# MXCHipConnector.net
KiCad netlist of a schematic drawn in EAGLE
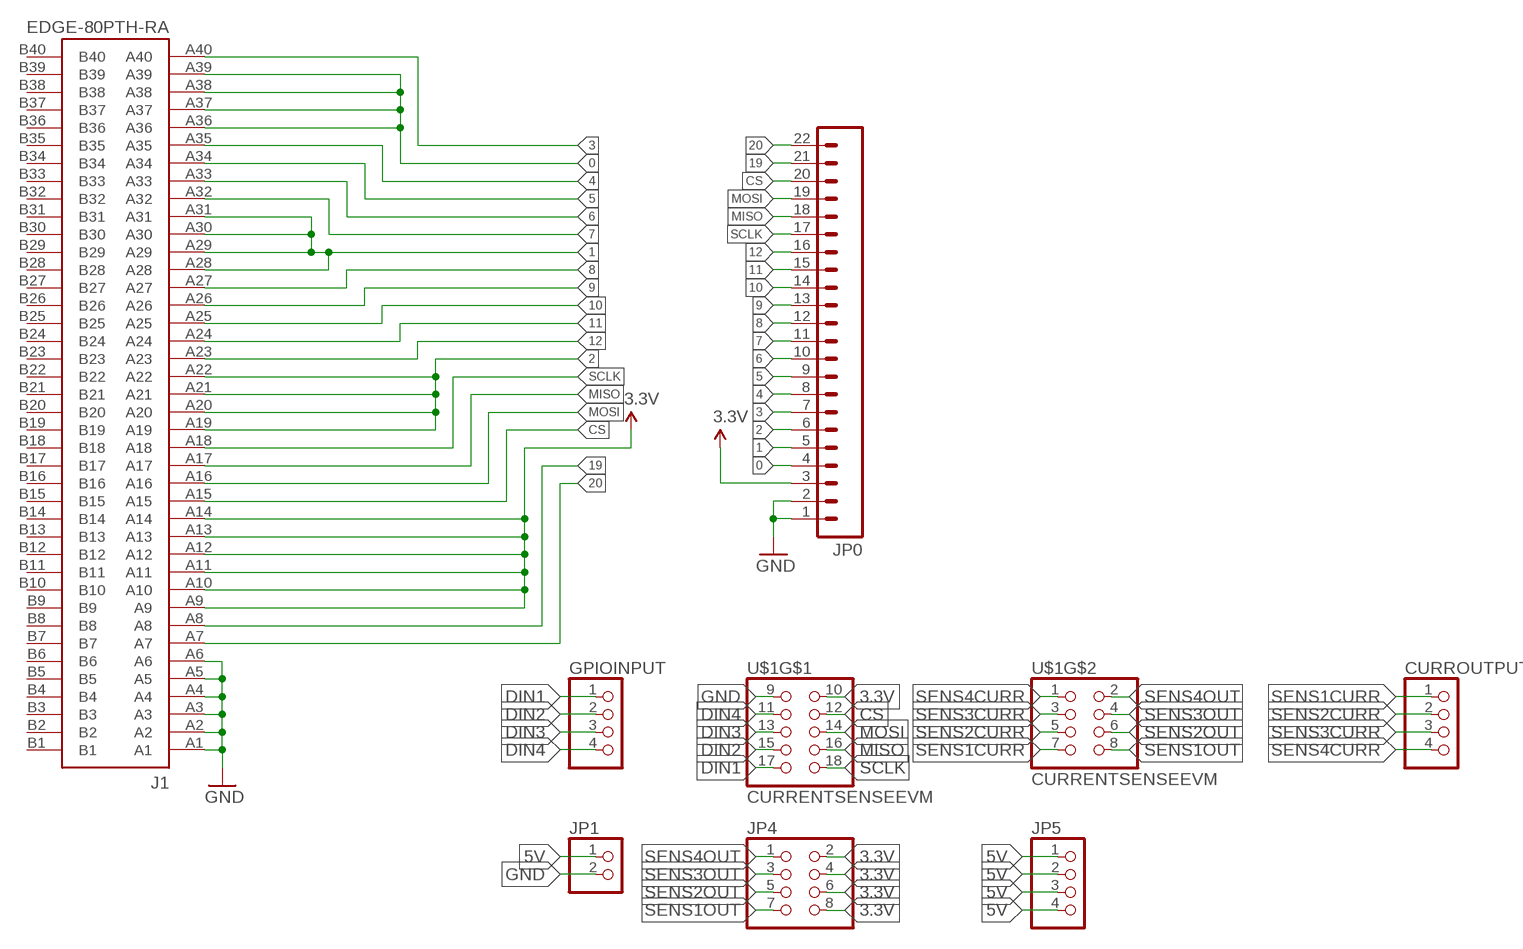
[diagram p0: schematic, sheet 1]

(export (version "E")
  (design (tool "Eeschema 10.0.6"))
  (components
    (comp (ref "CURROUTPUT")
      (value "PINHD-1X4")
      (footprint "eagle-import:1X04")
      (libsource (lib "eagle-import") (part "PINHD-1X4"))
    )
    (comp (ref "GPIOINPUT")
      (value "PINHD-1X4")
      (footprint "eagle-import:1X04")
      (libsource (lib "eagle-import") (part "PINHD-1X4"))
    )
    (comp (ref "J1")
      (value "EDGE-80PTH-RA")
      (footprint "eagle-import:VEC-127-080-R")
      (libsource (lib "eagle-import") (part "EDGE-80PTH-RA"))
    )
    (comp (ref "JP0")
      (value "M22PTH")
      (footprint "eagle-import:1X22")
      (libsource (lib "eagle-import") (part "M22PTH"))
    )
    (comp (ref "JP1")
      (value "PINHD-1X2")
      (footprint "eagle-import:1X02")
      (libsource (lib "eagle-import") (part "PINHD-1X2"))
    )
    (comp (ref "JP4")
      (value "PINHD-2X4")
      (footprint "eagle-import:2X04")
      (libsource (lib "eagle-import") (part "PINHD-2X4"))
    )
    (comp (ref "JP5")
      (value "PINHD-1X4")
      (footprint "eagle-import:1X04")
      (libsource (lib "eagle-import") (part "PINHD-1X4"))
    )
    (comp (ref "U$1")
      (value "CURRENTSENSEEVM")
      (footprint "eagle-import:CURRENTSENSEEVM")
      (libsource (lib "eagle-import") (part "CURRENTSENSEEVM"))
    )
  )
  (nets
    (net (code "1") (name "0") (class "Default")
      (node (ref "J1") (pin "A36") (pinfunction "A36_A36") (pintype "bidirectional"))
      (node (ref "J1") (pin "A37") (pinfunction "A37_A37") (pintype "bidirectional"))
      (node (ref "J1") (pin "A38") (pinfunction "A38_A38") (pintype "bidirectional"))
      (node (ref "J1") (pin "A39") (pinfunction "A39_A39") (pintype "bidirectional"))
      (node (ref "JP0") (pin "4") (pinfunction "4_4") (pintype "passive"))
    )
    (net (code "2") (name "1") (class "Default")
      (node (ref "J1") (pin "A28") (pinfunction "A28_A28") (pintype "bidirectional"))
      (node (ref "J1") (pin "A29") (pinfunction "A29_A29") (pintype "bidirectional"))
      (node (ref "J1") (pin "A30") (pinfunction "A30_A30") (pintype "bidirectional"))
      (node (ref "J1") (pin "A31") (pinfunction "A31_A31") (pintype "bidirectional"))
      (node (ref "JP0") (pin "5") (pinfunction "5_5") (pintype "passive"))
    )
    (net (code "3") (name "2") (class "Default")
      (node (ref "J1") (pin "A19") (pinfunction "A19_A19") (pintype "bidirectional"))
      (node (ref "J1") (pin "A20") (pinfunction "A20_A20") (pintype "bidirectional"))
      (node (ref "J1") (pin "A21") (pinfunction "A21_A21") (pintype "bidirectional"))
      (node (ref "J1") (pin "A22") (pinfunction "A22_A22") (pintype "bidirectional"))
      (node (ref "JP0") (pin "6") (pinfunction "6_6") (pintype "passive"))
    )
    (net (code "4") (name "3") (class "Default")
      (node (ref "J1") (pin "A40") (pinfunction "A40_A40") (pintype "bidirectional"))
      (node (ref "JP0") (pin "7") (pinfunction "7_7") (pintype "passive"))
    )
    (net (code "5") (name "3.3V") (class "Default")
      (node (ref "J1") (pin "A10") (pinfunction "A10_A10") (pintype "bidirectional"))
      (node (ref "J1") (pin "A11") (pinfunction "A11_A11") (pintype "bidirectional"))
      (node (ref "J1") (pin "A12") (pinfunction "A12_A12") (pintype "bidirectional"))
      (node (ref "J1") (pin "A13") (pinfunction "A13_A13") (pintype "bidirectional"))
      (node (ref "J1") (pin "A14") (pinfunction "A14_A14") (pintype "bidirectional"))
      (node (ref "J1") (pin "A9") (pinfunction "A9_A9") (pintype "bidirectional"))
      (node (ref "JP0") (pin "3") (pinfunction "3_3") (pintype "passive"))
      (node (ref "JP4") (pin "2") (pinfunction "2_2") (pintype "passive"))
      (node (ref "JP4") (pin "4") (pinfunction "4_4") (pintype "passive"))
      (node (ref "JP4") (pin "6") (pinfunction "6_6") (pintype "passive"))
      (node (ref "JP4") (pin "8") (pinfunction "8_8") (pintype "passive"))
      (node (ref "U$1") (pin "10") (pinfunction "2_10") (pintype "passive"))
    )
    (net (code "6") (name "4") (class "Default")
      (node (ref "J1") (pin "A35") (pinfunction "A35_A35") (pintype "bidirectional"))
      (node (ref "JP0") (pin "8") (pinfunction "8_8") (pintype "passive"))
    )
    (net (code "7") (name "5") (class "Default")
      (node (ref "J1") (pin "A34") (pinfunction "A34_A34") (pintype "bidirectional"))
      (node (ref "JP0") (pin "9") (pinfunction "9_9") (pintype "passive"))
    )
    (net (code "8") (name "5V") (class "Default")
      (node (ref "JP1") (pin "1") (pinfunction "1_1") (pintype "passive"))
      (node (ref "JP5") (pin "1") (pinfunction "1_1") (pintype "passive"))
      (node (ref "JP5") (pin "2") (pinfunction "2_2") (pintype "passive"))
      (node (ref "JP5") (pin "3") (pinfunction "3_3") (pintype "passive"))
      (node (ref "JP5") (pin "4") (pinfunction "4_4") (pintype "passive"))
    )
    (net (code "9") (name "6") (class "Default")
      (node (ref "J1") (pin "A33") (pinfunction "A33_A33") (pintype "bidirectional"))
      (node (ref "JP0") (pin "10") (pinfunction "10_10") (pintype "passive"))
    )
    (net (code "10") (name "7") (class "Default")
      (node (ref "J1") (pin "A32") (pinfunction "A32_A32") (pintype "bidirectional"))
      (node (ref "JP0") (pin "11") (pinfunction "11_11") (pintype "passive"))
    )
    (net (code "11") (name "8") (class "Default")
      (node (ref "J1") (pin "A27") (pinfunction "A27_A27") (pintype "bidirectional"))
      (node (ref "JP0") (pin "12") (pinfunction "12_12") (pintype "passive"))
    )
    (net (code "12") (name "9") (class "Default")
      (node (ref "J1") (pin "A26") (pinfunction "A26_A26") (pintype "bidirectional"))
      (node (ref "JP0") (pin "13") (pinfunction "13_13") (pintype "passive"))
    )
    (net (code "13") (name "10") (class "Default")
      (node (ref "J1") (pin "A25") (pinfunction "A25_A25") (pintype "bidirectional"))
      (node (ref "JP0") (pin "14") (pinfunction "14_14") (pintype "passive"))
    )
    (net (code "14") (name "11") (class "Default")
      (node (ref "J1") (pin "A24") (pinfunction "A24_A24") (pintype "bidirectional"))
      (node (ref "JP0") (pin "15") (pinfunction "15_15") (pintype "passive"))
    )
    (net (code "15") (name "12") (class "Default")
      (node (ref "J1") (pin "A23") (pinfunction "A23_A23") (pintype "bidirectional"))
      (node (ref "JP0") (pin "16") (pinfunction "16_16") (pintype "passive"))
    )
    (net (code "16") (name "19") (class "Default")
      (node (ref "J1") (pin "A8") (pinfunction "A8_A8") (pintype "bidirectional"))
      (node (ref "JP0") (pin "21") (pinfunction "21_21") (pintype "passive"))
    )
    (net (code "17") (name "20") (class "Default")
      (node (ref "J1") (pin "A7") (pinfunction "A7_A7") (pintype "bidirectional"))
      (node (ref "JP0") (pin "22") (pinfunction "22_22") (pintype "passive"))
    )
    (net (code "18") (name "CS") (class "Default")
      (node (ref "J1") (pin "A15") (pinfunction "A15_A15") (pintype "bidirectional"))
      (node (ref "JP0") (pin "20") (pinfunction "20_20") (pintype "passive"))
      (node (ref "U$1") (pin "12") (pinfunction "4_12") (pintype "passive"))
    )
    (net (code "19") (name "DIN1") (class "Default")
      (node (ref "GPIOINPUT") (pin "1") (pinfunction "1_1") (pintype "passive"))
      (node (ref "U$1") (pin "17") (pinfunction "9_17") (pintype "passive"))
    )
    (net (code "20") (name "DIN2") (class "Default")
      (node (ref "GPIOINPUT") (pin "2") (pinfunction "2_2") (pintype "passive"))
      (node (ref "U$1") (pin "15") (pinfunction "7_15") (pintype "passive"))
    )
    (net (code "21") (name "DIN3") (class "Default")
      (node (ref "GPIOINPUT") (pin "3") (pinfunction "3_3") (pintype "passive"))
      (node (ref "U$1") (pin "13") (pinfunction "5_13") (pintype "passive"))
    )
    (net (code "22") (name "DIN4") (class "Default")
      (node (ref "GPIOINPUT") (pin "4") (pinfunction "4_4") (pintype "passive"))
      (node (ref "U$1") (pin "11") (pinfunction "3_11") (pintype "passive"))
    )
    (net (code "23") (name "GND") (class "Default")
      (node (ref "J1") (pin "A1") (pinfunction "A1_A1") (pintype "bidirectional"))
      (node (ref "J1") (pin "A2") (pinfunction "A2_A2") (pintype "bidirectional"))
      (node (ref "J1") (pin "A3") (pinfunction "A3_A3") (pintype "bidirectional"))
      (node (ref "J1") (pin "A4") (pinfunction "A4_A4") (pintype "bidirectional"))
      (node (ref "J1") (pin "A5") (pinfunction "A5_A5") (pintype "bidirectional"))
      (node (ref "J1") (pin "A6") (pinfunction "A6_A6") (pintype "bidirectional"))
      (node (ref "JP0") (pin "1") (pinfunction "1_1") (pintype "passive"))
      (node (ref "JP0") (pin "2") (pinfunction "2_2") (pintype "passive"))
      (node (ref "JP1") (pin "2") (pinfunction "2_2") (pintype "passive"))
      (node (ref "U$1") (pin "9") (pinfunction "1_9") (pintype "passive"))
    )
    (net (code "24") (name "MISO") (class "Default")
      (node (ref "J1") (pin "A17") (pinfunction "A17_A17") (pintype "bidirectional"))
      (node (ref "JP0") (pin "18") (pinfunction "18_18") (pintype "passive"))
      (node (ref "U$1") (pin "16") (pinfunction "8_16") (pintype "passive"))
    )
    (net (code "25") (name "MOSI") (class "Default")
      (node (ref "J1") (pin "A16") (pinfunction "A16_A16") (pintype "bidirectional"))
      (node (ref "JP0") (pin "19") (pinfunction "19_19") (pintype "passive"))
      (node (ref "U$1") (pin "14") (pinfunction "6_14") (pintype "passive"))
    )
    (net (code "26") (name "SCLK") (class "Default")
      (node (ref "J1") (pin "A18") (pinfunction "A18_A18") (pintype "bidirectional"))
      (node (ref "JP0") (pin "17") (pinfunction "17_17") (pintype "passive"))
      (node (ref "U$1") (pin "18") (pinfunction "10_18") (pintype "passive"))
    )
    (net (code "27") (name "SENS1CURR") (class "Default")
      (node (ref "CURROUTPUT") (pin "1") (pinfunction "1_1") (pintype "passive"))
      (node (ref "U$1") (pin "7") (pinfunction "7_7") (pintype "passive"))
    )
    (net (code "28") (name "SENS1OUT") (class "Default")
      (node (ref "JP4") (pin "7") (pinfunction "7_7") (pintype "passive"))
      (node (ref "U$1") (pin "8") (pinfunction "8_8") (pintype "passive"))
    )
    (net (code "29") (name "SENS2CURR") (class "Default")
      (node (ref "CURROUTPUT") (pin "2") (pinfunction "2_2") (pintype "passive"))
      (node (ref "U$1") (pin "5") (pinfunction "5_5") (pintype "passive"))
    )
    (net (code "30") (name "SENS2OUT") (class "Default")
      (node (ref "JP4") (pin "5") (pinfunction "5_5") (pintype "passive"))
      (node (ref "U$1") (pin "6") (pinfunction "6_6") (pintype "passive"))
    )
    (net (code "31") (name "SENS3CURR") (class "Default")
      (node (ref "CURROUTPUT") (pin "3") (pinfunction "3_3") (pintype "passive"))
      (node (ref "U$1") (pin "3") (pinfunction "3_3") (pintype "passive"))
    )
    (net (code "32") (name "SENS3OUT") (class "Default")
      (node (ref "JP4") (pin "3") (pinfunction "3_3") (pintype "passive"))
      (node (ref "U$1") (pin "4") (pinfunction "4_4") (pintype "passive"))
    )
    (net (code "33") (name "SENS4CURR") (class "Default")
      (node (ref "CURROUTPUT") (pin "4") (pinfunction "4_4") (pintype "passive"))
      (node (ref "U$1") (pin "1") (pinfunction "1_1") (pintype "passive"))
    )
    (net (code "34") (name "SENS4OUT") (class "Default")
      (node (ref "JP4") (pin "1") (pinfunction "1_1") (pintype "passive"))
      (node (ref "U$1") (pin "2") (pinfunction "2_2") (pintype "passive"))
    )
    (net (code "35") (name "unconnected-(J1-PadB1)") (class "Default")
      (node (ref "J1") (pin "B1") (pinfunction "B1_B1") (pintype "bidirectional"))
    )
    (net (code "36") (name "unconnected-(J1-PadB2)") (class "Default")
      (node (ref "J1") (pin "B2") (pinfunction "B2_B2") (pintype "bidirectional"))
    )
    (net (code "37") (name "unconnected-(J1-PadB3)") (class "Default")
      (node (ref "J1") (pin "B3") (pinfunction "B3_B3") (pintype "bidirectional"))
    )
    (net (code "38") (name "unconnected-(J1-PadB4)") (class "Default")
      (node (ref "J1") (pin "B4") (pinfunction "B4_B4") (pintype "bidirectional"))
    )
    (net (code "39") (name "unconnected-(J1-PadB5)") (class "Default")
      (node (ref "J1") (pin "B5") (pinfunction "B5_B5") (pintype "bidirectional"))
    )
    (net (code "40") (name "unconnected-(J1-PadB6)") (class "Default")
      (node (ref "J1") (pin "B6") (pinfunction "B6_B6") (pintype "bidirectional"))
    )
    (net (code "41") (name "unconnected-(J1-PadB7)") (class "Default")
      (node (ref "J1") (pin "B7") (pinfunction "B7_B7") (pintype "bidirectional"))
    )
    (net (code "42") (name "unconnected-(J1-PadB8)") (class "Default")
      (node (ref "J1") (pin "B8") (pinfunction "B8_B8") (pintype "bidirectional"))
    )
    (net (code "43") (name "unconnected-(J1-PadB9)") (class "Default")
      (node (ref "J1") (pin "B9") (pinfunction "B9_B9") (pintype "bidirectional"))
    )
    (net (code "44") (name "unconnected-(J1-PadB10)") (class "Default")
      (node (ref "J1") (pin "B10") (pinfunction "B10_B10") (pintype "bidirectional"))
    )
    (net (code "45") (name "unconnected-(J1-PadB11)") (class "Default")
      (node (ref "J1") (pin "B11") (pinfunction "B11_B11") (pintype "bidirectional"))
    )
    (net (code "46") (name "unconnected-(J1-PadB12)") (class "Default")
      (node (ref "J1") (pin "B12") (pinfunction "B12_B12") (pintype "bidirectional"))
    )
    (net (code "47") (name "unconnected-(J1-PadB13)") (class "Default")
      (node (ref "J1") (pin "B13") (pinfunction "B13_B13") (pintype "bidirectional"))
    )
    (net (code "48") (name "unconnected-(J1-PadB14)") (class "Default")
      (node (ref "J1") (pin "B14") (pinfunction "B14_B14") (pintype "bidirectional"))
    )
    (net (code "49") (name "unconnected-(J1-PadB15)") (class "Default")
      (node (ref "J1") (pin "B15") (pinfunction "B15_B15") (pintype "bidirectional"))
    )
    (net (code "50") (name "unconnected-(J1-PadB16)") (class "Default")
      (node (ref "J1") (pin "B16") (pinfunction "B16_B16") (pintype "bidirectional"))
    )
    (net (code "51") (name "unconnected-(J1-PadB17)") (class "Default")
      (node (ref "J1") (pin "B17") (pinfunction "B17_B17") (pintype "bidirectional"))
    )
    (net (code "52") (name "unconnected-(J1-PadB18)") (class "Default")
      (node (ref "J1") (pin "B18") (pinfunction "B18_B18") (pintype "bidirectional"))
    )
    (net (code "53") (name "unconnected-(J1-PadB19)") (class "Default")
      (node (ref "J1") (pin "B19") (pinfunction "B19_B19") (pintype "bidirectional"))
    )
    (net (code "54") (name "unconnected-(J1-PadB20)") (class "Default")
      (node (ref "J1") (pin "B20") (pinfunction "B20_B20") (pintype "bidirectional"))
    )
    (net (code "55") (name "unconnected-(J1-PadB21)") (class "Default")
      (node (ref "J1") (pin "B21") (pinfunction "B21_B21") (pintype "bidirectional"))
    )
    (net (code "56") (name "unconnected-(J1-PadB22)") (class "Default")
      (node (ref "J1") (pin "B22") (pinfunction "B22_B22") (pintype "bidirectional"))
    )
    (net (code "57") (name "unconnected-(J1-PadB23)") (class "Default")
      (node (ref "J1") (pin "B23") (pinfunction "B23_B23") (pintype "bidirectional"))
    )
    (net (code "58") (name "unconnected-(J1-PadB24)") (class "Default")
      (node (ref "J1") (pin "B24") (pinfunction "B24_B24") (pintype "bidirectional"))
    )
    (net (code "59") (name "unconnected-(J1-PadB25)") (class "Default")
      (node (ref "J1") (pin "B25") (pinfunction "B25_B25") (pintype "bidirectional"))
    )
    (net (code "60") (name "unconnected-(J1-PadB26)") (class "Default")
      (node (ref "J1") (pin "B26") (pinfunction "B26_B26") (pintype "bidirectional"))
    )
    (net (code "61") (name "unconnected-(J1-PadB27)") (class "Default")
      (node (ref "J1") (pin "B27") (pinfunction "B27_B27") (pintype "bidirectional"))
    )
    (net (code "62") (name "unconnected-(J1-PadB28)") (class "Default")
      (node (ref "J1") (pin "B28") (pinfunction "B28_B28") (pintype "bidirectional"))
    )
    (net (code "63") (name "unconnected-(J1-PadB29)") (class "Default")
      (node (ref "J1") (pin "B29") (pinfunction "B29_B29") (pintype "bidirectional"))
    )
    (net (code "64") (name "unconnected-(J1-PadB30)") (class "Default")
      (node (ref "J1") (pin "B30") (pinfunction "B30_B30") (pintype "bidirectional"))
    )
    (net (code "65") (name "unconnected-(J1-PadB31)") (class "Default")
      (node (ref "J1") (pin "B31") (pinfunction "B31_B31") (pintype "bidirectional"))
    )
    (net (code "66") (name "unconnected-(J1-PadB32)") (class "Default")
      (node (ref "J1") (pin "B32") (pinfunction "B32_B32") (pintype "bidirectional"))
    )
    (net (code "67") (name "unconnected-(J1-PadB33)") (class "Default")
      (node (ref "J1") (pin "B33") (pinfunction "B33_B33") (pintype "bidirectional"))
    )
    (net (code "68") (name "unconnected-(J1-PadB34)") (class "Default")
      (node (ref "J1") (pin "B34") (pinfunction "B34_B34") (pintype "bidirectional"))
    )
    (net (code "69") (name "unconnected-(J1-PadB35)") (class "Default")
      (node (ref "J1") (pin "B35") (pinfunction "B35_B35") (pintype "bidirectional"))
    )
    (net (code "70") (name "unconnected-(J1-PadB36)") (class "Default")
      (node (ref "J1") (pin "B36") (pinfunction "B36_B36") (pintype "bidirectional"))
    )
    (net (code "71") (name "unconnected-(J1-PadB37)") (class "Default")
      (node (ref "J1") (pin "B37") (pinfunction "B37_B37") (pintype "bidirectional"))
    )
    (net (code "72") (name "unconnected-(J1-PadB38)") (class "Default")
      (node (ref "J1") (pin "B38") (pinfunction "B38_B38") (pintype "bidirectional"))
    )
    (net (code "73") (name "unconnected-(J1-PadB39)") (class "Default")
      (node (ref "J1") (pin "B39") (pinfunction "B39_B39") (pintype "bidirectional"))
    )
    (net (code "74") (name "unconnected-(J1-PadB40)") (class "Default")
      (node (ref "J1") (pin "B40") (pinfunction "B40_B40") (pintype "bidirectional"))
    )
  )
)
